# ESC_Tester_SCH.net
KiCad netlist of a schematic drawn in Altium Designer
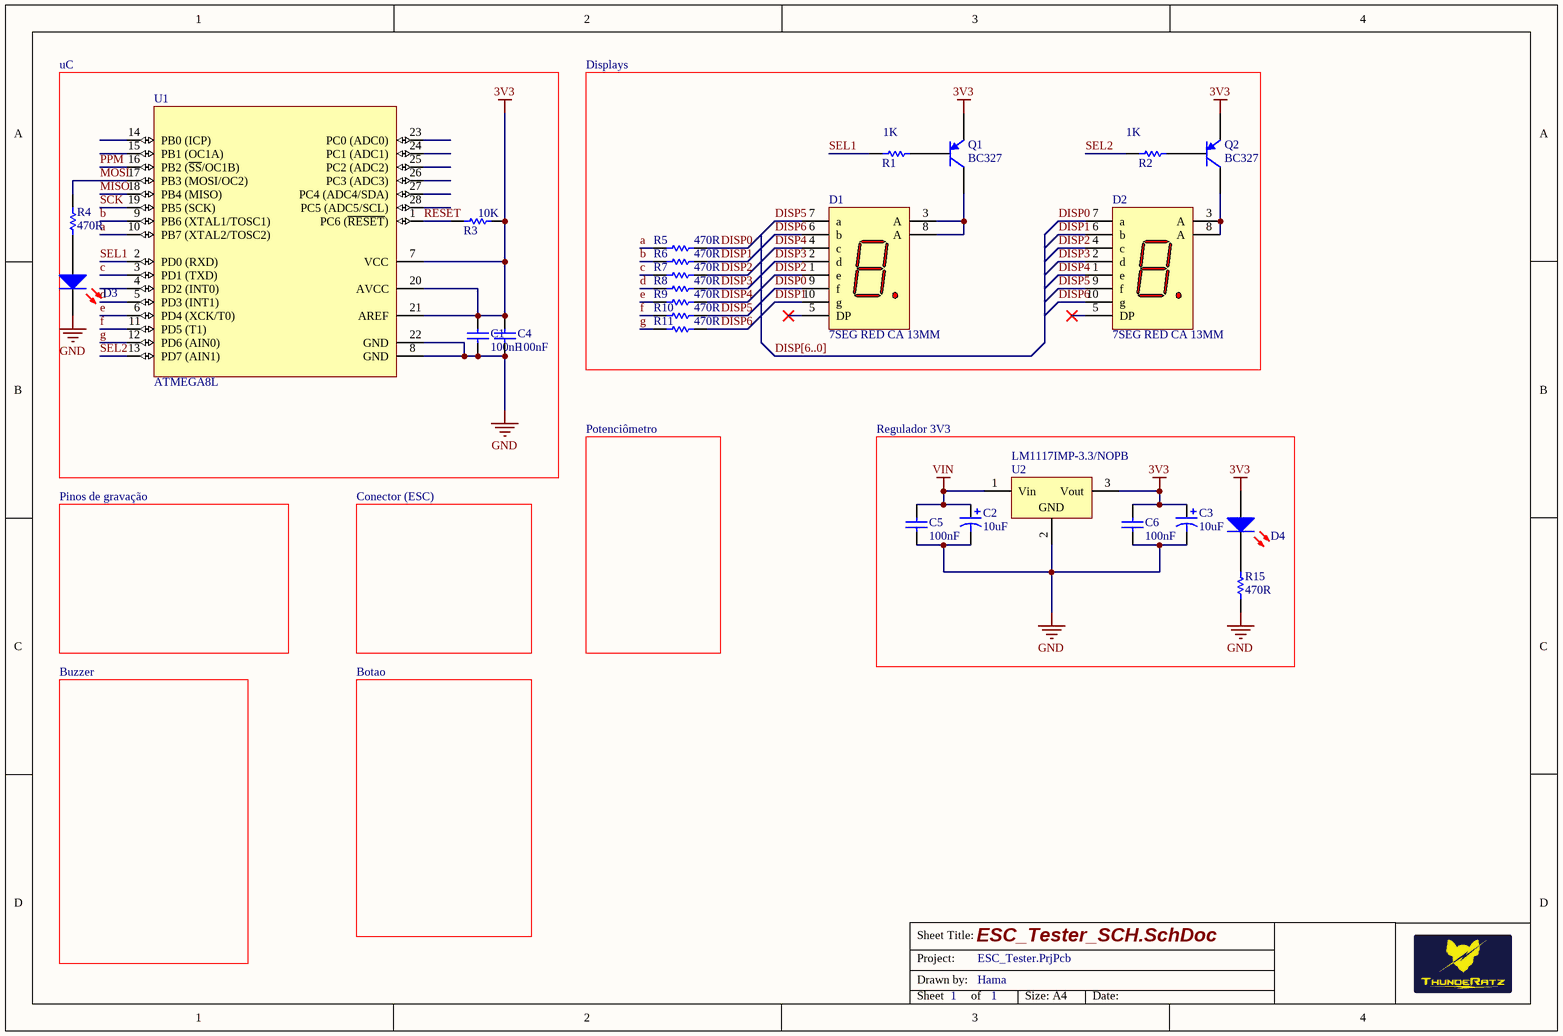
[diagram p0: ESC_Tester_SCH.SchDoc]

(export (version "E")
  (design (tool "Eeschema 10.0.6"))
  (components
    (comp (ref "C1")
      (value "Cap Film 0.1uF")
      (footprint "Cap Film 0.1uF")
      (description "Cap Film 0.1uF 63V PET 10% (7.2 X 2.5 X 6.5mm) Radial 5mm 125C Bulk")
      (fields
        (field (name "MANUFACTURER") "TDK EPCOS")
        (field (name "MANUFACTURER PART NUMBER") "B32529C104K")
        (field (name "CAPACITANCE") "100nF")
      )
      (libsource (lib "ESC_Tester_SCHLIB") (part "Cap Film 0.1uF - B32529C104K"))
    )
    (comp (ref "C2")
      (value "10uF")
      (footprint "CAP RAD 10UF 35V")
      (description "CAP ELE RAD 10uF 16V")
      (fields (field (name "MANUFACTURER PART NUMBER") "IMP1295"))
      (libsource (lib "ESC_Tester_SCHLIB") (part "CAP ELE RAD 10uF 16V"))
    )
    (comp (ref "C3")
      (value "10uF")
      (footprint "CAP RAD 10UF 35V")
      (description "CAP ELE RAD 10uF 16V")
      (fields (field (name "MANUFACTURER PART NUMBER") "IMP1295"))
      (libsource (lib "ESC_Tester_SCHLIB") (part "CAP ELE RAD 10uF 16V"))
    )
    (comp (ref "C4")
      (value "Cap Film 0.1uF")
      (footprint "Cap Film 0.1uF")
      (description "Cap Film 0.1uF 63V PET 10% (7.2 X 2.5 X 6.5mm) Radial 5mm 125C Bulk")
      (fields
        (field (name "MANUFACTURER") "TDK EPCOS")
        (field (name "MANUFACTURER PART NUMBER") "B32529C104K")
        (field (name "CAPACITANCE") "100nF")
      )
      (libsource (lib "ESC_Tester_SCHLIB") (part "Cap Film 0.1uF - B32529C104K"))
    )
    (comp (ref "C5")
      (value "Cap Film 0.1uF")
      (footprint "Cap Film 0.1uF")
      (description "Cap Film 0.1uF 63V PET 10% (7.2 X 2.5 X 6.5mm) Radial 5mm 125C Bulk")
      (fields
        (field (name "MANUFACTURER") "TDK EPCOS")
        (field (name "MANUFACTURER PART NUMBER") "B32529C104K")
        (field (name "CAPACITANCE") "100nF")
      )
      (libsource (lib "ESC_Tester_SCHLIB") (part "Cap Film 0.1uF - B32529C104K"))
    )
    (comp (ref "C6")
      (value "Cap Film 0.1uF")
      (footprint "Cap Film 0.1uF")
      (description "Cap Film 0.1uF 63V PET 10% (7.2 X 2.5 X 6.5mm) Radial 5mm 125C Bulk")
      (fields
        (field (name "MANUFACTURER") "TDK EPCOS")
        (field (name "MANUFACTURER PART NUMBER") "B32529C104K")
        (field (name "CAPACITANCE") "100nF")
      )
      (libsource (lib "ESC_Tester_SCHLIB") (part "Cap Film 0.1uF - B32529C104K"))
    )
    (comp (ref "D1")
      (value "7SEG RED CA 13MM")
      (footprint "7SEG RED PTH")
      (description "PHOTONIC - PHDE113A - DISPLAY, SEVEN SEGMENT, 13MM, RED")
      (fields (field (name "MANUFACTURER") "Photonic") (field (name "MANUFACTURER PART NUMBER") "PHDE113A"))
      (libsource (lib "PS_LIB_SCH") (part "7SEG RED CA 13MM"))
    )
    (comp (ref "D2")
      (value "7SEG RED CA 13MM")
      (footprint "7SEG RED PTH")
      (description "PHOTONIC - PHDE113A - DISPLAY, SEVEN SEGMENT, 13MM, RED")
      (fields (field (name "MANUFACTURER") "Photonic") (field (name "MANUFACTURER PART NUMBER") "PHDE113A"))
      (libsource (lib "PS_LIB_SCH") (part "7SEG RED CA 13MM"))
    )
    (comp (ref "D3")
      (value "LED 5MM RED")
      (footprint "LED 5MM RED")
      (fields (field (name "MANUFACTURER") "Paralight") (field (name "MANUFACTURER PART NUMBER") "IMP585"))
      (libsource (lib "ESC_Tester_SCHLIB") (part "LED 5MM RED"))
    )
    (comp (ref "D4")
      (value "LED 5MM RED")
      (footprint "LED 5MM RED")
      (fields (field (name "MANUFACTURER") "Paralight") (field (name "MANUFACTURER PART NUMBER") "IMP585"))
      (libsource (lib "ESC_Tester_SCHLIB") (part "LED 5MM RED"))
    )
    (comp (ref "Q1")
      (value "BC327")
      (footprint "TO92")
      (description "Bipolar Transistors - BJT PNP -45V -800mA HFE/630")
      (fields (field (name "MANUFACTURER") "Fairchild Semiconductor"))
      (libsource (lib "PS_LIB_SCH") (part "BC327 BJT PNP TO92"))
    )
    (comp (ref "Q2")
      (value "BC327")
      (footprint "TO92")
      (description "Bipolar Transistors - BJT PNP -45V -800mA HFE/630")
      (fields (field (name "MANUFACTURER") "Fairchild Semiconductor"))
      (libsource (lib "PS_LIB_SCH") (part "BC327 BJT PNP TO92"))
    )
    (comp (ref "R1")
      (value "RES 1K 1/4W CARBON FILM")
      (footprint "RES 1K 1/4W CARBON FILM")
      (description "RES 1K OHM 1/4W 5% CARBON FILM")
      (fields
        (field (name "MANUFACTURER") "Ty-Ohm")
        (field (name "MANUFACTURER PART NUMBER") "CR25")
        (field (name "RESISTANCE (OHMS)") "1K")
      )
      (libsource (lib "PS_LIB_SCH") (part "RES 1K 1/4W CARBON FILM"))
    )
    (comp (ref "R2")
      (value "RES 1K 1/4W CARBON FILM")
      (footprint "RES 1K 1/4W CARBON FILM")
      (description "RES 1K OHM 1/4W 5% CARBON FILM")
      (fields
        (field (name "MANUFACTURER") "Ty-Ohm")
        (field (name "MANUFACTURER PART NUMBER") "CR25")
        (field (name "RESISTANCE (OHMS)") "1K")
      )
      (libsource (lib "PS_LIB_SCH") (part "RES 1K 1/4W CARBON FILM"))
    )
    (comp (ref "R3")
      (value "RES 10K 1/4W CARBON FILM")
      (footprint "RES 10K 1/4W CARBON FILM")
      (description "RES 10K OHM 1/4W 5% CARBON FILM")
      (fields
        (field (name "MANUFACTURER") "Ty-Ohm")
        (field (name "MANUFACTURER PART NUMBER") "CR25")
        (field (name "RESISTANCE (OHMS)") "10K")
      )
      (libsource (lib "ESC_Tester_SCHLIB") (part "RES 10K 1/4W CARBON FILM"))
    )
    (comp (ref "R4")
      (value "RES 470R 1/4W CARBON FILM")
      (footprint "RES 470R 1/4W CARBON FILM_STAND")
      (description "RES 470R OHM 1/4W 5% CARBON FILM")
      (fields
        (field (name "MANUFACTURER") "Ty-Ohm")
        (field (name "MANUFACTURER PART NUMBER") "CR25")
        (field (name "RESISTANCE (OHMS)") "470R")
      )
      (libsource (lib "ESC_Tester_SCHLIB") (part "RES 470R 1/4W CARBON FILM"))
    )
    (comp (ref "R5")
      (value "RES 470R 1/4W CARBON FILM")
      (footprint "RES 470R 1/4W CARBON FILM")
      (description "RES 470R OHM 1/4W 5% CARBON FILM")
      (fields
        (field (name "MANUFACTURER") "Ty-Ohm")
        (field (name "MANUFACTURER PART NUMBER") "CR25")
        (field (name "RESISTANCE (OHMS)") "470R")
      )
      (libsource (lib "PS_LIB_SCH") (part "RES 470R 1/4W CARBON FILM"))
    )
    (comp (ref "R6")
      (value "RES 470R 1/4W CARBON FILM")
      (footprint "RES 470R 1/4W CARBON FILM")
      (description "RES 470R OHM 1/4W 5% CARBON FILM")
      (fields
        (field (name "MANUFACTURER") "Ty-Ohm")
        (field (name "MANUFACTURER PART NUMBER") "CR25")
        (field (name "RESISTANCE (OHMS)") "470R")
      )
      (libsource (lib "PS_LIB_SCH") (part "RES 470R 1/4W CARBON FILM"))
    )
    (comp (ref "R7")
      (value "RES 470R 1/4W CARBON FILM")
      (footprint "RES 470R 1/4W CARBON FILM")
      (description "RES 470R OHM 1/4W 5% CARBON FILM")
      (fields
        (field (name "MANUFACTURER") "Ty-Ohm")
        (field (name "MANUFACTURER PART NUMBER") "CR25")
        (field (name "RESISTANCE (OHMS)") "470R")
      )
      (libsource (lib "PS_LIB_SCH") (part "RES 470R 1/4W CARBON FILM"))
    )
    (comp (ref "R8")
      (value "RES 470R 1/4W CARBON FILM")
      (footprint "RES 470R 1/4W CARBON FILM")
      (description "RES 470R OHM 1/4W 5% CARBON FILM")
      (fields
        (field (name "MANUFACTURER") "Ty-Ohm")
        (field (name "MANUFACTURER PART NUMBER") "CR25")
        (field (name "RESISTANCE (OHMS)") "470R")
      )
      (libsource (lib "PS_LIB_SCH") (part "RES 470R 1/4W CARBON FILM"))
    )
    (comp (ref "R9")
      (value "RES 470R 1/4W CARBON FILM")
      (footprint "RES 470R 1/4W CARBON FILM")
      (description "RES 470R OHM 1/4W 5% CARBON FILM")
      (fields
        (field (name "MANUFACTURER") "Ty-Ohm")
        (field (name "MANUFACTURER PART NUMBER") "CR25")
        (field (name "RESISTANCE (OHMS)") "470R")
      )
      (libsource (lib "PS_LIB_SCH") (part "RES 470R 1/4W CARBON FILM"))
    )
    (comp (ref "R10")
      (value "RES 470R 1/4W CARBON FILM")
      (footprint "RES 470R 1/4W CARBON FILM")
      (description "RES 470R OHM 1/4W 5% CARBON FILM")
      (fields
        (field (name "MANUFACTURER") "Ty-Ohm")
        (field (name "MANUFACTURER PART NUMBER") "CR25")
        (field (name "RESISTANCE (OHMS)") "470R")
      )
      (libsource (lib "PS_LIB_SCH") (part "RES 470R 1/4W CARBON FILM"))
    )
    (comp (ref "R11")
      (value "RES 470R 1/4W CARBON FILM")
      (footprint "RES 470R 1/4W CARBON FILM")
      (description "RES 470R OHM 1/4W 5% CARBON FILM")
      (fields
        (field (name "MANUFACTURER") "Ty-Ohm")
        (field (name "MANUFACTURER PART NUMBER") "CR25")
        (field (name "RESISTANCE (OHMS)") "470R")
      )
      (libsource (lib "PS_LIB_SCH") (part "RES 470R 1/4W CARBON FILM"))
    )
    (comp (ref "R15")
      (value "RES 470R 1/4W CARBON FILM")
      (footprint "RES 470R 1/4W CARBON FILM_STAND")
      (description "RES 470R OHM 1/4W 5% CARBON FILM")
      (fields
        (field (name "MANUFACTURER") "Ty-Ohm")
        (field (name "MANUFACTURER PART NUMBER") "CR25")
        (field (name "RESISTANCE (OHMS)") "470R")
      )
      (libsource (lib "ESC_Tester_SCHLIB") (part "RES 470R 1/4W CARBON FILM"))
    )
    (comp (ref "U1")
      (value "ATMEGA8L")
      (footprint "DIP28")
      (description "8-bit Microcontrollers - MCU 8kB Flash 0.5kB EEPROM 23 I/O Pins")
      (fields (field (name "MANUFACTURER") "Atmel") (field (name "MANUFACTURER PART NUMBER") "ATmega8L-8PU"))
      (libsource (lib "PS_LIB_SCH") (part "MCU ATMEGA8L-8PU PDIP28_1"))
    )
    (comp (ref "U2")
      (value "LM1117IMP-3.3/NOPB")
      (footprint "TO220AB")
      (description "TEXAS INSTRUMENTS   LM1117IMP-3.3/NOPB   LDO, 1.2VDO, 3.3V, 1%, 0.8A, 3SOT223")
      (fields (field (name "MANUFACTURER") "Texas Instruments"))
      (libsource (lib "ESC_Tester_SCHLIB") (part "LM1117IMP-3.3/NOPB"))
    )
  )
  (nets
    (net (code "1") (name "/DISP0") (class "Default")
      (node (ref "D1") (pin "9") (pinfunction "f_9") (pintype "passive"))
      (node (ref "D2") (pin "7") (pinfunction "a_7") (pintype "passive"))
      (node (ref "R5") (pin "2") (pinfunction "2_2") (pintype "passive"))
    )
    (net (code "2") (name "/DISP1") (class "Default")
      (node (ref "D1") (pin "10") (pinfunction "g_10") (pintype "passive"))
      (node (ref "D2") (pin "6") (pinfunction "b_6") (pintype "passive"))
      (node (ref "R6") (pin "2") (pinfunction "2_2") (pintype "passive"))
    )
    (net (code "3") (name "/DISP2") (class "Default")
      (node (ref "D1") (pin "1") (pinfunction "e_1") (pintype "passive"))
      (node (ref "D2") (pin "4") (pinfunction "c_4") (pintype "passive"))
      (node (ref "R7") (pin "2") (pinfunction "2_2") (pintype "passive"))
    )
    (net (code "4") (name "/DISP3") (class "Default")
      (node (ref "D1") (pin "2") (pinfunction "d_2") (pintype "passive"))
      (node (ref "D2") (pin "2") (pinfunction "d_2") (pintype "passive"))
      (node (ref "R8") (pin "2") (pinfunction "2_2") (pintype "passive"))
    )
    (net (code "5") (name "/DISP4") (class "Default")
      (node (ref "D1") (pin "4") (pinfunction "c_4") (pintype "passive"))
      (node (ref "D2") (pin "1") (pinfunction "e_1") (pintype "passive"))
      (node (ref "R9") (pin "2") (pinfunction "2_2") (pintype "passive"))
    )
    (net (code "6") (name "/DISP5") (class "Default")
      (node (ref "D1") (pin "7") (pinfunction "a_7") (pintype "passive"))
      (node (ref "D2") (pin "9") (pinfunction "f_9") (pintype "passive"))
      (node (ref "R10") (pin "2") (pinfunction "2_2") (pintype "passive"))
    )
    (net (code "7") (name "/DISP6") (class "Default")
      (node (ref "D1") (pin "6") (pinfunction "b_6") (pintype "passive"))
      (node (ref "D2") (pin "10") (pinfunction "g_10") (pintype "passive"))
      (node (ref "R11") (pin "2") (pinfunction "2_2") (pintype "passive"))
    )
    (net (code "9") (name "/MISO") (class "Default")
      (node (ref "U1") (pin "18") (pinfunction "PB4_(MISO)_18") (pintype "bidirectional"))
    )
    (net (code "10") (name "/MOSI") (class "Default")
      (node (ref "R4") (pin "2") (pinfunction "2_2") (pintype "passive"))
      (node (ref "U1") (pin "17") (pinfunction "PB3_(MOSI/OC2)_17") (pintype "bidirectional"))
    )
    (net (code "11") (name "/PPM") (class "Default")
      (node (ref "U1") (pin "16") (pinfunction "PB2_(~{SS}/OC1B)_16") (pintype "bidirectional"))
    )
    (net (code "12") (name "/RESET") (class "Default")
      (node (ref "R3") (pin "1") (pinfunction "1_1") (pintype "passive"))
      (node (ref "U1") (pin "1") (pinfunction "PC6_(~{RESET})_1") (pintype "bidirectional"))
    )
    (net (code "13") (name "/SCK") (class "Default")
      (node (ref "U1") (pin "19") (pinfunction "PB5_(SCK)_19") (pintype "bidirectional"))
    )
    (net (code "14") (name "/SEL1") (class "Default")
      (node (ref "R1") (pin "1") (pinfunction "1_1") (pintype "passive"))
      (node (ref "U1") (pin "2") (pinfunction "PD0_(RXD)_2") (pintype "bidirectional"))
    )
    (net (code "15") (name "/SEL2") (class "Default")
      (node (ref "R2") (pin "1") (pinfunction "1_1") (pintype "passive"))
      (node (ref "U1") (pin "13") (pinfunction "PD7_(AIN1)_13") (pintype "bidirectional"))
    )
    (net (code "16") (name "/a") (class "Default")
      (node (ref "R5") (pin "1") (pinfunction "1_1") (pintype "passive"))
      (node (ref "U1") (pin "10") (pinfunction "PB7_(XTAL2/TOSC2)_10") (pintype "bidirectional"))
    )
    (net (code "17") (name "/b") (class "Default")
      (node (ref "R6") (pin "1") (pinfunction "1_1") (pintype "passive"))
      (node (ref "U1") (pin "9") (pinfunction "PB6_(XTAL1/TOSC1)_9") (pintype "bidirectional"))
    )
    (net (code "18") (name "/c") (class "Default")
      (node (ref "R7") (pin "1") (pinfunction "1_1") (pintype "passive"))
      (node (ref "U1") (pin "3") (pinfunction "PD1_(TXD)_3") (pintype "bidirectional"))
    )
    (net (code "19") (name "/d") (class "Default")
      (node (ref "R8") (pin "1") (pinfunction "1_1") (pintype "passive"))
      (node (ref "U1") (pin "5") (pinfunction "PD3_(INT1)_5") (pintype "bidirectional"))
    )
    (net (code "20") (name "/e") (class "Default")
      (node (ref "R9") (pin "1") (pinfunction "1_1") (pintype "passive"))
      (node (ref "U1") (pin "6") (pinfunction "PD4_(XCK/T0)_6") (pintype "bidirectional"))
    )
    (net (code "21") (name "/f") (class "Default")
      (node (ref "R10") (pin "1") (pinfunction "1_1") (pintype "passive"))
      (node (ref "U1") (pin "11") (pinfunction "PD5_(T1)_11") (pintype "bidirectional"))
    )
    (net (code "22") (name "/g") (class "Default")
      (node (ref "R11") (pin "1") (pinfunction "1_1") (pintype "passive"))
      (node (ref "U1") (pin "12") (pinfunction "PD6_(AIN0)_12") (pintype "bidirectional"))
    )
    (net (code "23") (name "3V3") (class "Default")
      (node (ref "C1") (pin "2") (pinfunction "2_2") (pintype "passive"))
      (node (ref "C3") (pin "1") (pinfunction "1_1") (pintype "passive"))
      (node (ref "C4") (pin "2") (pinfunction "2_2") (pintype "passive"))
      (node (ref "C6") (pin "2") (pinfunction "2_2") (pintype "passive"))
      (node (ref "D4") (pin "1") (pinfunction "A_1") (pintype "passive"))
      (node (ref "Q1") (pin "3") (pinfunction "E_3") (pintype "passive"))
      (node (ref "Q2") (pin "3") (pinfunction "E_3") (pintype "passive"))
      (node (ref "R3") (pin "2") (pinfunction "2_2") (pintype "passive"))
      (node (ref "U1") (pin "20") (pinfunction "AVCC_20") (pintype "power_in"))
      (node (ref "U1") (pin "21") (pinfunction "AREF_21") (pintype "passive"))
      (node (ref "U1") (pin "7") (pinfunction "VCC_7") (pintype "power_in"))
      (node (ref "U2") (pin "3") (pinfunction "Vout_3") (pintype "passive"))
    )
    (net (code "24") (name "GND") (class "Default")
      (node (ref "C1") (pin "1") (pinfunction "1_1") (pintype "passive"))
      (node (ref "C2") (pin "2") (pinfunction "2_2") (pintype "passive"))
      (node (ref "C3") (pin "2") (pinfunction "2_2") (pintype "passive"))
      (node (ref "C4") (pin "1") (pinfunction "1_1") (pintype "passive"))
      (node (ref "C5") (pin "1") (pinfunction "1_1") (pintype "passive"))
      (node (ref "C6") (pin "1") (pinfunction "1_1") (pintype "passive"))
      (node (ref "D3") (pin "2") (pinfunction "K_2") (pintype "passive"))
      (node (ref "R15") (pin "2") (pinfunction "2_2") (pintype "passive"))
      (node (ref "U1") (pin "22") (pinfunction "GND_22") (pintype "power_in"))
      (node (ref "U1") (pin "8") (pinfunction "GND_8") (pintype "power_in"))
      (node (ref "U2") (pin "2") (pinfunction "GND_2") (pintype "passive"))
    )
    (net (code "25") (name "Net-(D3-A)") (class "Default")
      (node (ref "D3") (pin "1") (pinfunction "A_1") (pintype "passive"))
      (node (ref "R4") (pin "1") (pinfunction "1_1") (pintype "passive"))
    )
    (net (code "26") (name "Net-(D4-K)") (class "Default")
      (node (ref "D4") (pin "2") (pinfunction "K_2") (pintype "passive"))
      (node (ref "R15") (pin "1") (pinfunction "1_1") (pintype "passive"))
    )
    (net (code "27") (name "Net-(Q1-B)") (class "Default")
      (node (ref "Q1") (pin "2") (pinfunction "B_2") (pintype "passive"))
      (node (ref "R1") (pin "2") (pinfunction "2_2") (pintype "passive"))
    )
    (net (code "28") (name "Net-(Q1-C)") (class "Default")
      (node (ref "D1") (pin "3") (pinfunction "A_3") (pintype "passive"))
      (node (ref "D1") (pin "8") (pinfunction "A_8") (pintype "passive"))
      (node (ref "Q1") (pin "1") (pinfunction "C_1") (pintype "passive"))
    )
    (net (code "29") (name "Net-(Q2-B)") (class "Default")
      (node (ref "Q2") (pin "2") (pinfunction "B_2") (pintype "passive"))
      (node (ref "R2") (pin "2") (pinfunction "2_2") (pintype "passive"))
    )
    (net (code "30") (name "Net-(Q2-C)") (class "Default")
      (node (ref "D2") (pin "3") (pinfunction "A_3") (pintype "passive"))
      (node (ref "D2") (pin "8") (pinfunction "A_8") (pintype "passive"))
      (node (ref "Q2") (pin "1") (pinfunction "C_1") (pintype "passive"))
    )
    (net (code "31") (name "VIN") (class "Default")
      (node (ref "C2") (pin "1") (pinfunction "1_1") (pintype "passive"))
      (node (ref "C5") (pin "2") (pinfunction "2_2") (pintype "passive"))
      (node (ref "U2") (pin "1") (pinfunction "Vin_1") (pintype "passive"))
    )
    (net (code "32") (name "unconnected-(D1-DP-Pad5)") (class "Default")
      (node (ref "D1") (pin "5") (pinfunction "DP_5") (pintype "passive+no_connect"))
    )
    (net (code "33") (name "unconnected-(D2-DP-Pad5)") (class "Default")
      (node (ref "D2") (pin "5") (pinfunction "DP_5") (pintype "passive+no_connect"))
    )
    (net (code "34") (name "unconnected-(U1-PB0_(ICP)-Pad14)") (class "Default")
      (node (ref "U1") (pin "14") (pinfunction "PB0_(ICP)_14") (pintype "bidirectional"))
    )
    (net (code "35") (name "unconnected-(U1-PB1_(OC1A)-Pad15)") (class "Default")
      (node (ref "U1") (pin "15") (pinfunction "PB1_(OC1A)_15") (pintype "bidirectional"))
    )
    (net (code "36") (name "unconnected-(U1-PC0_(ADC0)-Pad23)") (class "Default")
      (node (ref "U1") (pin "23") (pinfunction "PC0_(ADC0)_23") (pintype "bidirectional"))
    )
    (net (code "37") (name "unconnected-(U1-PC1_(ADC1)-Pad24)") (class "Default")
      (node (ref "U1") (pin "24") (pinfunction "PC1_(ADC1)_24") (pintype "bidirectional"))
    )
    (net (code "38") (name "unconnected-(U1-PC2_(ADC2)-Pad25)") (class "Default")
      (node (ref "U1") (pin "25") (pinfunction "PC2_(ADC2)_25") (pintype "bidirectional"))
    )
    (net (code "39") (name "unconnected-(U1-PC3_(ADC3)-Pad26)") (class "Default")
      (node (ref "U1") (pin "26") (pinfunction "PC3_(ADC3)_26") (pintype "bidirectional"))
    )
    (net (code "40") (name "unconnected-(U1-PC4_(ADC4{slash}SDA)-Pad27)") (class "Default")
      (node (ref "U1") (pin "27") (pinfunction "PC4_(ADC4/SDA)_27") (pintype "bidirectional"))
    )
    (net (code "41") (name "unconnected-(U1-PC5_(ADC5{slash}SCL)-Pad28)") (class "Default")
      (node (ref "U1") (pin "28") (pinfunction "PC5_(ADC5/SCL)_28") (pintype "bidirectional"))
    )
    (net (code "42") (name "unconnected-(U1-PD2_(INT0)-Pad4)") (class "Default")
      (node (ref "U1") (pin "4") (pinfunction "PD2_(INT0)_4") (pintype "bidirectional"))
    )
  )
)
